# XCF08PFS48C_FLASH.net
KiCad netlist of a schematic drawn in Altium Designer
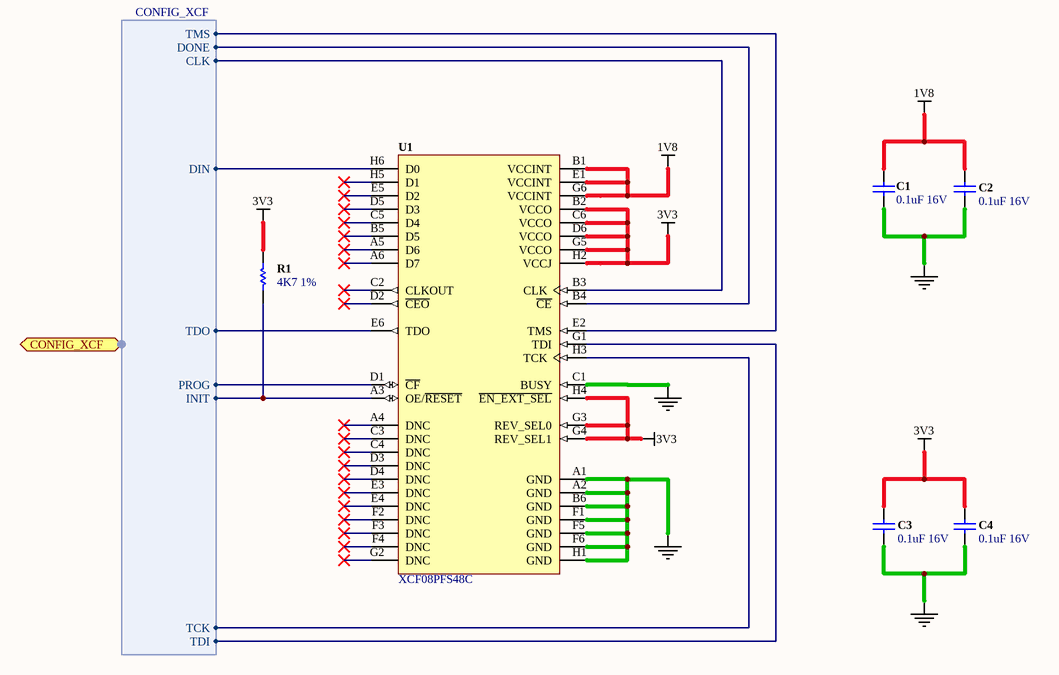
[diagram p0: XCF08PFS48C_FLASH.SchDoc]

(export (version "E")
  (design (tool "Eeschema 10.0.6"))
  (components
    (comp (ref "C1")
      (value "0.1uF 16V")
      (footprint "CAPC1005-STAR")
      (description "Capacitor, Ceramic, 0.1uF 10% 16V 0402 (1005) X7R")
      (fields (field (name "TOLERANCE") "10 %"))
      (libsource (lib "altium-import") (part "root_2_CAP-NP_"))
    )
    (comp (ref "C2")
      (value "0.1uF 16V")
      (footprint "CAPC1005-STAR")
      (description "Capacitor, Ceramic, 0.1uF 10% 16V 0402 (1005) X7R")
      (fields (field (name "TOLERANCE") "10 %"))
      (libsource (lib "altium-import") (part "root_0_CAP-NP_"))
    )
    (comp (ref "C3")
      (value "0.1uF 16V")
      (footprint "CAPC1005-STAR")
      (description "Capacitor, Ceramic, 0.1uF 10% 16V 0402 (1005) X7R")
      (fields (field (name "TOLERANCE") "10 %"))
      (libsource (lib "altium-import") (part "root_0_CAP-NP_"))
    )
    (comp (ref "C4")
      (value "0.1uF 16V")
      (footprint "CAPC1005-STAR")
      (description "Capacitor, Ceramic, 0.1uF 10% 16V 0402 (1005) X7R")
      (fields (field (name "TOLERANCE") "10 %"))
      (libsource (lib "altium-import") (part "root_0_CAP-NP_"))
    )
    (comp (ref "R1")
      (value "4K7 1%")
      (footprint "RESC1005-STAR")
      (description "Resistor, 4K7 1% 0402 (1005)")
      (fields (field (name "TOLERANCE") "1 %"))
      (libsource (lib "altium-import") (part "root_0_mirrored_RES_"))
    )
    (comp (ref "U1")
      (value "XCF08PFS48C")
      (footprint "BGA80P8X6-48")
      (libsource (lib "altium-import") (part "root_0_mirrored_XCF08-PFS48_"))
    )
  )
  (nets
    (net (code "2") (name "/CLK") (class "Default")
      (node (ref "U1") (pin "B3") (pinfunction "CLK_B3") (pintype "input"))
    )
    (net (code "3") (name "/DIN") (class "Default")
      (node (ref "U1") (pin "H6") (pinfunction "D0_H6") (pintype "tri_state"))
    )
    (net (code "4") (name "/DONE") (class "Default")
      (node (ref "U1") (pin "B4") (pinfunction "~{CE}_B4") (pintype "input"))
    )
    (net (code "5") (name "/INIT") (class "Default")
      (node (ref "R1") (pin "2") (pinfunction "2_2") (pintype "passive"))
      (node (ref "U1") (pin "A3") (pinfunction "OE/~{RESET}_A3") (pintype "bidirectional"))
    )
    (net (code "6") (name "/PROG") (class "Default")
      (node (ref "U1") (pin "D1") (pinfunction "~{CF}_D1") (pintype "bidirectional"))
    )
    (net (code "7") (name "/TCK") (class "Default")
      (node (ref "U1") (pin "H3") (pinfunction "TCK_H3") (pintype "input"))
    )
    (net (code "8") (name "/TDI") (class "Default")
      (node (ref "U1") (pin "G1") (pinfunction "TDI_G1") (pintype "input"))
    )
    (net (code "9") (name "/TDO") (class "Default")
      (node (ref "U1") (pin "E6") (pinfunction "TDO_E6") (pintype "output"))
    )
    (net (code "10") (name "/TMS") (class "Default")
      (node (ref "U1") (pin "E2") (pinfunction "TMS_E2") (pintype "input"))
    )
    (net (code "12") (name "1V8") (class "Default")
      (node (ref "C1") (pin "2") (pinfunction "2_2") (pintype "passive"))
      (node (ref "C2") (pin "1") (pinfunction "1_1") (pintype "passive"))
      (node (ref "U1") (pin "B1") (pinfunction "VCCINT_B1") (pintype "power_in"))
      (node (ref "U1") (pin "E1") (pinfunction "VCCINT_E1") (pintype "power_in"))
      (node (ref "U1") (pin "G6") (pinfunction "VCCINT_G6") (pintype "power_in"))
    )
    (net (code "13") (name "3V3") (class "Default")
      (node (ref "C3") (pin "1") (pinfunction "1_1") (pintype "passive"))
      (node (ref "C4") (pin "1") (pinfunction "1_1") (pintype "passive"))
      (node (ref "R1") (pin "1") (pinfunction "1_1") (pintype "passive"))
      (node (ref "U1") (pin "B2") (pinfunction "VCCO_B2") (pintype "power_in"))
      (node (ref "U1") (pin "C6") (pinfunction "VCCO_C6") (pintype "power_in"))
      (node (ref "U1") (pin "D6") (pinfunction "VCCO_D6") (pintype "power_in"))
      (node (ref "U1") (pin "G3") (pinfunction "REV_SEL0_G3") (pintype "input"))
      (node (ref "U1") (pin "G4") (pinfunction "REV_SEL1_G4") (pintype "input"))
      (node (ref "U1") (pin "G5") (pinfunction "VCCO_G5") (pintype "power_in"))
      (node (ref "U1") (pin "H2") (pinfunction "VCCJ_H2") (pintype "power_in"))
      (node (ref "U1") (pin "H4") (pinfunction "~{EN_EXT_SEL}_H4") (pintype "input"))
    )
    (net (code "14") (name "GND") (class "Default")
      (node (ref "C1") (pin "1") (pinfunction "1_1") (pintype "passive"))
      (node (ref "C2") (pin "2") (pinfunction "2_2") (pintype "passive"))
      (node (ref "C3") (pin "2") (pinfunction "2_2") (pintype "passive"))
      (node (ref "C4") (pin "2") (pinfunction "2_2") (pintype "passive"))
      (node (ref "U1") (pin "A1") (pinfunction "GND_A1") (pintype "power_in"))
      (node (ref "U1") (pin "A2") (pinfunction "GND_A2") (pintype "power_in"))
      (node (ref "U1") (pin "B6") (pinfunction "GND_B6") (pintype "power_in"))
      (node (ref "U1") (pin "C1") (pinfunction "BUSY_C1") (pintype "input"))
      (node (ref "U1") (pin "F1") (pinfunction "GND_F1") (pintype "power_in"))
      (node (ref "U1") (pin "F5") (pinfunction "GND_F5") (pintype "power_in"))
      (node (ref "U1") (pin "F6") (pinfunction "GND_F6") (pintype "power_in"))
      (node (ref "U1") (pin "H1") (pinfunction "GND_H1") (pintype "power_in"))
    )
    (net (code "15") (name "unconnected-(U1-CLKOUT-PadC2)") (class "Default")
      (node (ref "U1") (pin "C2") (pinfunction "CLKOUT_C2") (pintype "output+no_connect"))
    )
    (net (code "16") (name "unconnected-(U1-D1-PadH5)") (class "Default")
      (node (ref "U1") (pin "H5") (pinfunction "D1_H5") (pintype "tri_state+no_connect"))
    )
    (net (code "17") (name "unconnected-(U1-D2-PadE5)") (class "Default")
      (node (ref "U1") (pin "E5") (pinfunction "D2_E5") (pintype "tri_state+no_connect"))
    )
    (net (code "18") (name "unconnected-(U1-D3-PadD5)") (class "Default")
      (node (ref "U1") (pin "D5") (pinfunction "D3_D5") (pintype "tri_state+no_connect"))
    )
    (net (code "19") (name "unconnected-(U1-D4-PadC5)") (class "Default")
      (node (ref "U1") (pin "C5") (pinfunction "D4_C5") (pintype "tri_state+no_connect"))
    )
    (net (code "20") (name "unconnected-(U1-D5-PadB5)") (class "Default")
      (node (ref "U1") (pin "B5") (pinfunction "D5_B5") (pintype "tri_state+no_connect"))
    )
    (net (code "21") (name "unconnected-(U1-D6-PadA5)") (class "Default")
      (node (ref "U1") (pin "A5") (pinfunction "D6_A5") (pintype "tri_state+no_connect"))
    )
    (net (code "22") (name "unconnected-(U1-D7-PadA6)") (class "Default")
      (node (ref "U1") (pin "A6") (pinfunction "D7_A6") (pintype "tri_state+no_connect"))
    )
    (net (code "23") (name "unconnected-(U1-DNC-PadA4)") (class "Default")
      (node (ref "U1") (pin "A4") (pinfunction "DNC_A4") (pintype "passive+no_connect"))
    )
    (net (code "24") (name "unconnected-(U1-DNC-PadC3)") (class "Default")
      (node (ref "U1") (pin "C3") (pinfunction "DNC_C3") (pintype "passive+no_connect"))
    )
    (net (code "25") (name "unconnected-(U1-DNC-PadC4)") (class "Default")
      (node (ref "U1") (pin "C4") (pinfunction "DNC_C4") (pintype "passive+no_connect"))
    )
    (net (code "26") (name "unconnected-(U1-DNC-PadD3)") (class "Default")
      (node (ref "U1") (pin "D3") (pinfunction "DNC_D3") (pintype "passive+no_connect"))
    )
    (net (code "27") (name "unconnected-(U1-DNC-PadD4)") (class "Default")
      (node (ref "U1") (pin "D4") (pinfunction "DNC_D4") (pintype "passive+no_connect"))
    )
    (net (code "28") (name "unconnected-(U1-DNC-PadE3)") (class "Default")
      (node (ref "U1") (pin "E3") (pinfunction "DNC_E3") (pintype "passive+no_connect"))
    )
    (net (code "29") (name "unconnected-(U1-DNC-PadE4)") (class "Default")
      (node (ref "U1") (pin "E4") (pinfunction "DNC_E4") (pintype "passive+no_connect"))
    )
    (net (code "30") (name "unconnected-(U1-DNC-PadF2)") (class "Default")
      (node (ref "U1") (pin "F2") (pinfunction "DNC_F2") (pintype "passive+no_connect"))
    )
    (net (code "31") (name "unconnected-(U1-DNC-PadF3)") (class "Default")
      (node (ref "U1") (pin "F3") (pinfunction "DNC_F3") (pintype "passive+no_connect"))
    )
    (net (code "32") (name "unconnected-(U1-DNC-PadF4)") (class "Default")
      (node (ref "U1") (pin "F4") (pinfunction "DNC_F4") (pintype "passive+no_connect"))
    )
    (net (code "33") (name "unconnected-(U1-DNC-PadG2)") (class "Default")
      (node (ref "U1") (pin "G2") (pinfunction "DNC_G2") (pintype "passive+no_connect"))
    )
    (net (code "34") (name "unconnected-(U1-~{CEO}-PadD2)") (class "Default")
      (node (ref "U1") (pin "D2") (pinfunction "~{CEO}_D2") (pintype "output+no_connect"))
    )
  )
)
